# mainboard.net
KiCad netlist of a schematic drawn in EAGLE
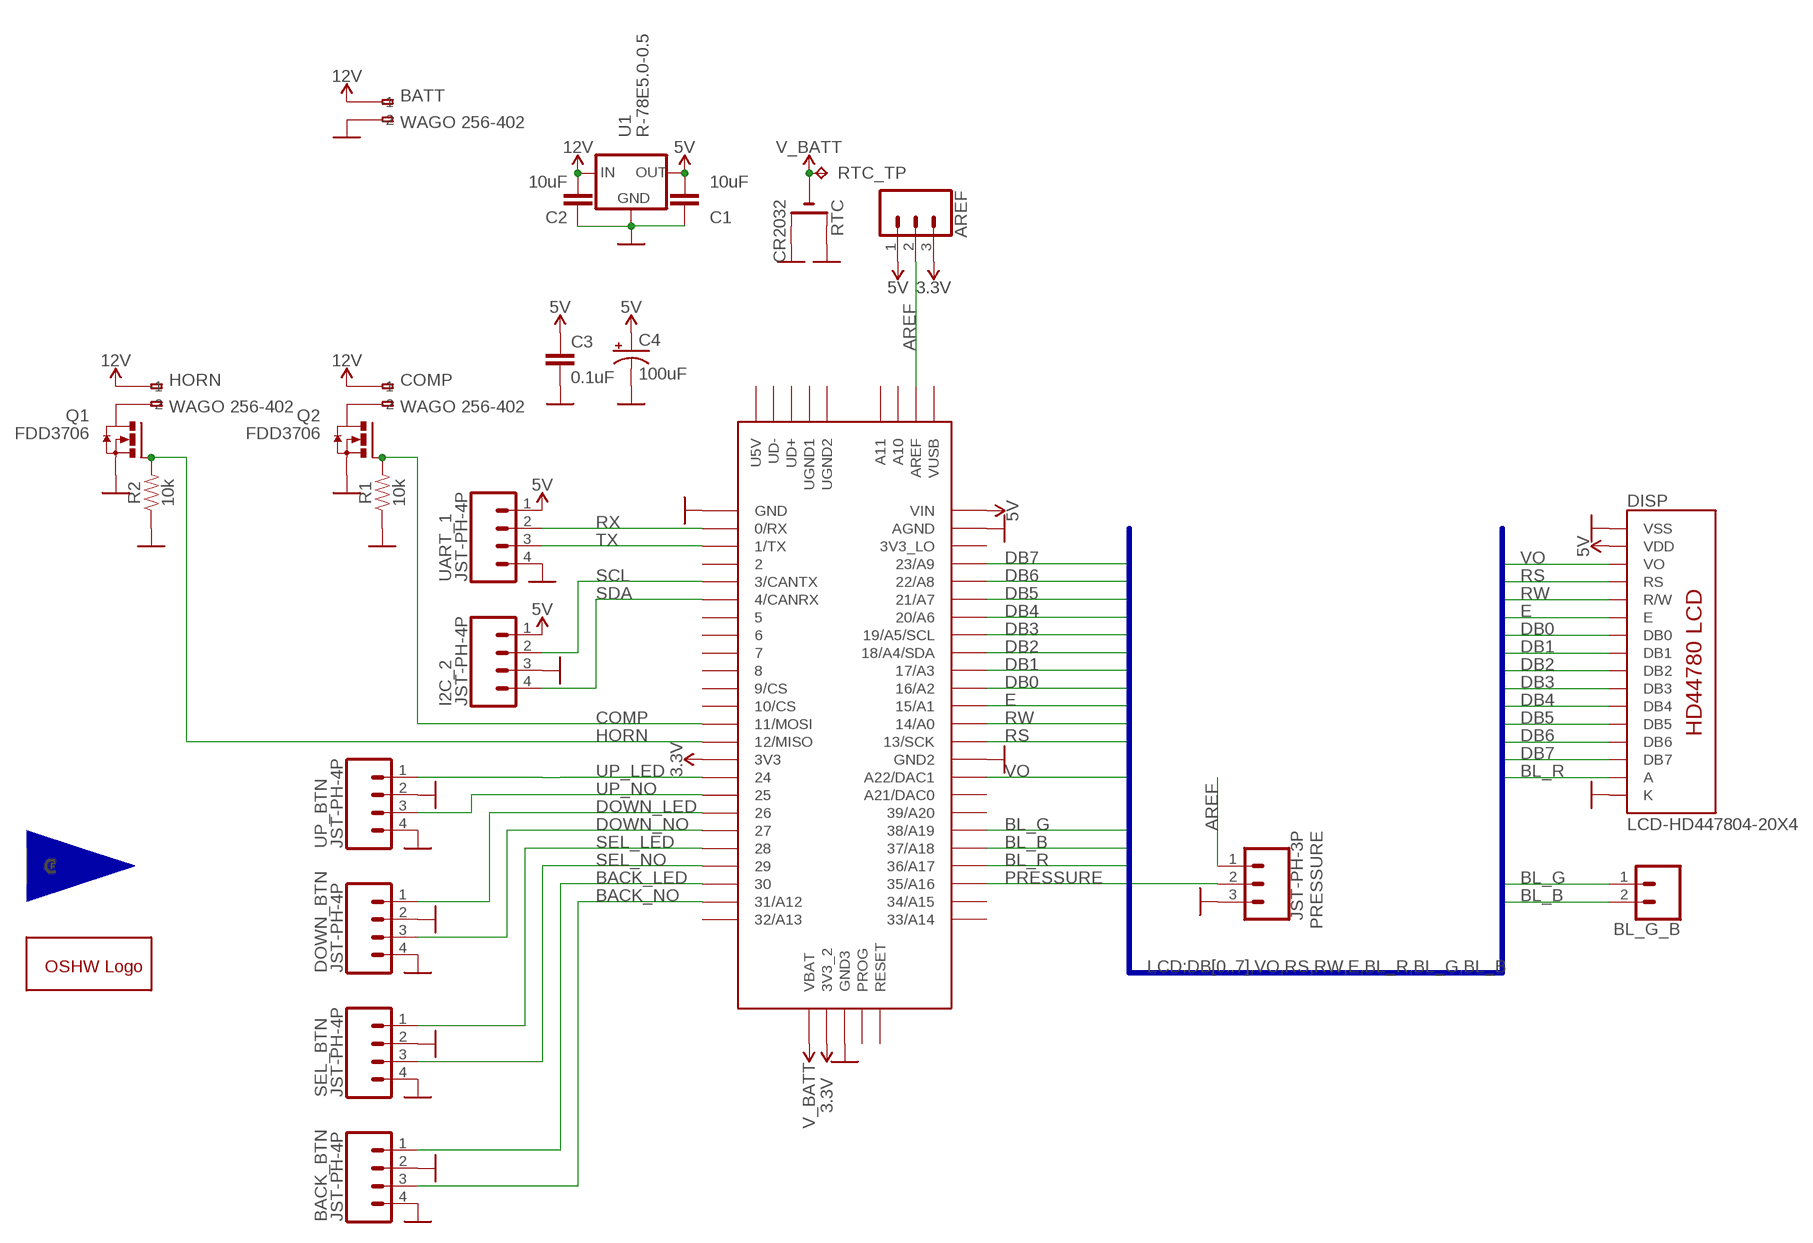
[diagram p0: schematic, sheet 1]

(export (version "E")
  (design (tool "Eeschema 10.0.6"))
  (components
    (comp (ref "AREF")
      (value "CONN_03LOCK")
      (footprint "eagle-import:1X03_LOCK")
      (libsource (lib "eagle-import") (part "CONN_03LOCK"))
    )
    (comp (ref "BACK_BTN")
      (value "JST-PH-4P")
      (footprint "eagle-import:JST-4-PTH-VERT")
      (libsource (lib "eagle-import") (part "CONN_04JST-PTH-VERT"))
    )
    (comp (ref "BATT")
      (value "WAGO 256-402")
      (footprint "eagle-import:255-402-5")
      (libsource (lib "eagle-import") (part "255-402-5"))
    )
    (comp (ref "BL_G_B")
      (value "CONN_02")
      (footprint "eagle-import:1X02")
      (libsource (lib "eagle-import") (part "CONN_02"))
    )
    (comp (ref "C1")
      (value "10uF")
      (footprint "eagle-import:0603")
      (libsource (lib "eagle-import") (part "10UF-0603-6.3V-20%"))
    )
    (comp (ref "C2")
      (value "10uF")
      (footprint "eagle-import:0603")
      (libsource (lib "eagle-import") (part "10UF-0603-6.3V-20%"))
    )
    (comp (ref "C3")
      (value "0.1uF")
      (footprint "eagle-import:0603")
      (libsource (lib "eagle-import") (part "0.1UF-0603-25V-(+80/-20%)"))
    )
    (comp (ref "C4")
      (value "100uF")
      (footprint "eagle-import:NIC_10X10.5_CAP")
      (libsource (lib "eagle-import") (part "100UF-POLAR-10X10.5-63V-20%"))
    )
    (comp (ref "COMP")
      (value "WAGO 256-402")
      (footprint "eagle-import:255-402-5")
      (libsource (lib "eagle-import") (part "255-402-5"))
    )
    (comp (ref "DISP")
      (value "LCD-HD447804-20X4")
      (footprint "eagle-import:LCD-20X4-4HOLES")
      (libsource (lib "eagle-import") (part "LCD-HD4478020X4-4HOLES4-HOLES"))
    )
    (comp (ref "DOWN_BTN")
      (value "JST-PH-4P")
      (footprint "eagle-import:JST-4-PTH-VERT")
      (libsource (lib "eagle-import") (part "CONN_04JST-PTH-VERT"))
    )
    (comp (ref "GOLD_ORB_SM1")
      (value "OSHWLOGOLOGO8MM")
      (footprint "eagle-import:OSHW_8MM")
      (libsource (lib "eagle-import") (part "OSHWLOGOLOGO8MM"))
    )
    (comp (ref "HORN")
      (value "WAGO 256-402")
      (footprint "eagle-import:255-402-5")
      (libsource (lib "eagle-import") (part "255-402-5"))
    )
    (comp (ref "I2C_2")
      (value "JST-PH-4P")
      (footprint "eagle-import:JST-4-PTH-VERT")
      (libsource (lib "eagle-import") (part "CONN_04JST-PTH-VERT"))
    )
    (comp (ref "PRESSURE")
      (value "JST-PH-3P")
      (footprint "eagle-import:JST-3-PTH-VERT")
      (libsource (lib "eagle-import") (part "CONN_03JST-PTH-VERT"))
    )
    (comp (ref "Q1")
      (value "FDD3706")
      (footprint "eagle-import:D2PACK")
      (libsource (lib "eagle-import") (part "IRF3704S"))
    )
    (comp (ref "Q2")
      (value "FDD3706")
      (footprint "eagle-import:D2PACK")
      (libsource (lib "eagle-import") (part "IRF3704S"))
    )
    (comp (ref "R1")
      (value "10k")
      (footprint "eagle-import:0603")
      (libsource (lib "eagle-import") (part "10KOHM-0603-1/10W-1%"))
    )
    (comp (ref "R2")
      (value "10k")
      (footprint "eagle-import:0603")
      (libsource (lib "eagle-import") (part "10KOHM-0603-1/10W-1%"))
    )
    (comp (ref "RTC")
      (value "CR2032")
      (footprint "eagle-import:CR2032-SMD")
      (libsource (lib "eagle-import") (part "CR2032SMT"))
    )
    (comp (ref "RTC_TP")
      (value "TPPAD1-17")
      (footprint "eagle-import:P1-17")
      (libsource (lib "eagle-import") (part "TPPAD1-17"))
    )
    (comp (ref "SEL_BTN")
      (value "JST-PH-4P")
      (footprint "eagle-import:JST-4-PTH-VERT")
      (libsource (lib "eagle-import") (part "CONN_04JST-PTH-VERT"))
    )
    (comp (ref "TEENSY")
      (value "TEENSY_3.5/3.6")
      (footprint "eagle-import:TEENSY_3.5_3.6")
      (libsource (lib "eagle-import") (part "TEENSY_3.5/3.6"))
    )
    (comp (ref "U$1")
      (value "CFLOGO")
      (footprint "eagle-import:CFLOGO")
      (libsource (lib "eagle-import") (part "CFLOGO"))
    )
    (comp (ref "U1")
      (value "R-78E5.0-0.5")
      (footprint "eagle-import:DC-DC_CONVERTER_78XX")
      (libsource (lib "eagle-import") (part "R-78E5.0-1.0"))
    )
    (comp (ref "UART_1")
      (value "JST-PH-4P")
      (footprint "eagle-import:JST-4-PTH-VERT")
      (libsource (lib "eagle-import") (part "CONN_04JST-PTH-VERT"))
    )
    (comp (ref "UP_BTN")
      (value "JST-PH-4P")
      (footprint "eagle-import:JST-4-PTH-VERT")
      (libsource (lib "eagle-import") (part "CONN_04JST-PTH-VERT"))
    )
  )
  (nets
    (net (code "1") (name "/AREF") (class "Default")
      (node (ref "AREF") (pin "2") (pinfunction "2_2") (pintype "passive"))
      (node (ref "PRESSURE") (pin "1") (pinfunction "1_1") (pintype "passive"))
      (node (ref "TEENSY") (pin "AREF") (pinfunction "AREF_AREF") (pintype "bidirectional"))
    )
    (net (code "2") (name "/BACK_LED") (class "Default")
      (node (ref "BACK_BTN") (pin "1") (pinfunction "1_1") (pintype "passive"))
      (node (ref "TEENSY") (pin "30") (pinfunction "30_30") (pintype "bidirectional"))
    )
    (net (code "3") (name "/BACK_NO") (class "Default")
      (node (ref "BACK_BTN") (pin "3") (pinfunction "3_3") (pintype "passive"))
      (node (ref "TEENSY") (pin "31/A12") (pinfunction "31/A12_31/A12") (pintype "bidirectional"))
    )
    (net (code "4") (name "/BL_B") (class "Default")
      (node (ref "BL_G_B") (pin "2") (pinfunction "2_2") (pintype "passive"))
      (node (ref "TEENSY") (pin "37/A18") (pinfunction "37/A18_37/A18") (pintype "bidirectional"))
    )
    (net (code "5") (name "/BL_G") (class "Default")
      (node (ref "BL_G_B") (pin "1") (pinfunction "1_1") (pintype "passive"))
      (node (ref "TEENSY") (pin "38/A19") (pinfunction "38/A19_38/A19") (pintype "bidirectional"))
    )
    (net (code "6") (name "/BL_R") (class "Default")
      (node (ref "DISP") (pin "P$15") (pinfunction "A_P$15") (pintype "power_in"))
      (node (ref "TEENSY") (pin "36/A17") (pinfunction "36/A17_36/A17") (pintype "bidirectional"))
    )
    (net (code "7") (name "/COMP") (class "Default")
      (node (ref "Q2") (pin "1") (pinfunction "G_1") (pintype "passive"))
      (node (ref "R1") (pin "2") (pinfunction "2_2") (pintype "passive"))
      (node (ref "TEENSY") (pin "11/MOSI") (pinfunction "11/MOSI_11/MOSI") (pintype "bidirectional"))
    )
    (net (code "8") (name "/DB0") (class "Default")
      (node (ref "DISP") (pin "P$7") (pinfunction "DB0_P$7") (pintype "bidirectional"))
      (node (ref "TEENSY") (pin "16/A2") (pinfunction "16/A2_16/A2") (pintype "bidirectional"))
    )
    (net (code "9") (name "/DB1") (class "Default")
      (node (ref "DISP") (pin "P$8") (pinfunction "DB1_P$8") (pintype "bidirectional"))
      (node (ref "TEENSY") (pin "17/A3") (pinfunction "17/A3_17/A3") (pintype "bidirectional"))
    )
    (net (code "10") (name "/DB2") (class "Default")
      (node (ref "DISP") (pin "P$9") (pinfunction "DB2_P$9") (pintype "bidirectional"))
      (node (ref "TEENSY") (pin "18/A4/SDA") (pinfunction "18/A4/SDA_18/A4/SDA") (pintype "bidirectional"))
    )
    (net (code "11") (name "/DB3") (class "Default")
      (node (ref "DISP") (pin "P$10") (pinfunction "DB3_P$10") (pintype "bidirectional"))
      (node (ref "TEENSY") (pin "19/A5/SCL") (pinfunction "19/A5/SCL_19/A5/SCL") (pintype "bidirectional"))
    )
    (net (code "12") (name "/DB4") (class "Default")
      (node (ref "DISP") (pin "P$11") (pinfunction "DB4_P$11") (pintype "bidirectional"))
      (node (ref "TEENSY") (pin "20/A6") (pinfunction "20/A6_20/A6") (pintype "bidirectional"))
    )
    (net (code "13") (name "/DB5") (class "Default")
      (node (ref "DISP") (pin "P$12") (pinfunction "DB5_P$12") (pintype "bidirectional"))
      (node (ref "TEENSY") (pin "21/A7") (pinfunction "21/A7_21/A7") (pintype "bidirectional"))
    )
    (net (code "14") (name "/DB6") (class "Default")
      (node (ref "DISP") (pin "P$13") (pinfunction "DB6_P$13") (pintype "bidirectional"))
      (node (ref "TEENSY") (pin "22/A8") (pinfunction "22/A8_22/A8") (pintype "bidirectional"))
    )
    (net (code "15") (name "/DB7") (class "Default")
      (node (ref "DISP") (pin "P$14") (pinfunction "DB7_P$14") (pintype "bidirectional"))
      (node (ref "TEENSY") (pin "23/A9") (pinfunction "23/A9_23/A9") (pintype "bidirectional"))
    )
    (net (code "16") (name "/DOWN_LED") (class "Default")
      (node (ref "DOWN_BTN") (pin "1") (pinfunction "1_1") (pintype "passive"))
      (node (ref "TEENSY") (pin "26") (pinfunction "26_26") (pintype "bidirectional"))
    )
    (net (code "17") (name "/DOWN_NO") (class "Default")
      (node (ref "DOWN_BTN") (pin "3") (pinfunction "3_3") (pintype "passive"))
      (node (ref "TEENSY") (pin "27") (pinfunction "27_27") (pintype "bidirectional"))
    )
    (net (code "18") (name "/E") (class "Default")
      (node (ref "DISP") (pin "P$6") (pinfunction "E_P$6") (pintype "input"))
      (node (ref "TEENSY") (pin "15/A1") (pinfunction "15/A1_15/A1") (pintype "bidirectional"))
    )
    (net (code "19") (name "/HORN") (class "Default")
      (node (ref "Q1") (pin "1") (pinfunction "G_1") (pintype "passive"))
      (node (ref "R2") (pin "2") (pinfunction "2_2") (pintype "passive"))
      (node (ref "TEENSY") (pin "12/MISO") (pinfunction "12/MISO_12/MISO") (pintype "bidirectional"))
    )
    (net (code "20") (name "/PRESSURE") (class "Default")
      (node (ref "PRESSURE") (pin "2") (pinfunction "2_2") (pintype "passive"))
      (node (ref "TEENSY") (pin "35/A16") (pinfunction "35/A16_35/A16") (pintype "bidirectional"))
    )
    (net (code "21") (name "/RS") (class "Default")
      (node (ref "DISP") (pin "P$4") (pinfunction "RS_P$4") (pintype "input"))
      (node (ref "TEENSY") (pin "13/SCK") (pinfunction "13/SCK_13/SCK") (pintype "bidirectional"))
    )
    (net (code "22") (name "/RW") (class "Default")
      (node (ref "DISP") (pin "P$5") (pinfunction "R/W_P$5") (pintype "input"))
      (node (ref "TEENSY") (pin "14/A0") (pinfunction "14/A0_14/A0") (pintype "bidirectional"))
    )
    (net (code "23") (name "/RX") (class "Default")
      (node (ref "TEENSY") (pin "0/RX") (pinfunction "0/RX_0/RX") (pintype "bidirectional"))
      (node (ref "UART_1") (pin "2") (pinfunction "2_2") (pintype "passive"))
    )
    (net (code "24") (name "/SCL") (class "Default")
      (node (ref "I2C_2") (pin "2") (pinfunction "2_2") (pintype "passive"))
      (node (ref "TEENSY") (pin "3/CANTX") (pinfunction "3/CANTX_3/CANTX") (pintype "bidirectional"))
    )
    (net (code "25") (name "/SDA") (class "Default")
      (node (ref "I2C_2") (pin "4") (pinfunction "4_4") (pintype "passive"))
      (node (ref "TEENSY") (pin "4/CANRX") (pinfunction "4/CANRX_4/CANRX") (pintype "bidirectional"))
    )
    (net (code "26") (name "/SEL_LED") (class "Default")
      (node (ref "SEL_BTN") (pin "1") (pinfunction "1_1") (pintype "passive"))
      (node (ref "TEENSY") (pin "28") (pinfunction "28_28") (pintype "bidirectional"))
    )
    (net (code "27") (name "/SEL_NO") (class "Default")
      (node (ref "SEL_BTN") (pin "3") (pinfunction "3_3") (pintype "passive"))
      (node (ref "TEENSY") (pin "29") (pinfunction "29_29") (pintype "bidirectional"))
    )
    (net (code "28") (name "/TX") (class "Default")
      (node (ref "TEENSY") (pin "1/TX") (pinfunction "1/TX_1/TX") (pintype "bidirectional"))
      (node (ref "UART_1") (pin "3") (pinfunction "3_3") (pintype "passive"))
    )
    (net (code "29") (name "/UP_LED") (class "Default")
      (node (ref "TEENSY") (pin "24") (pinfunction "24_24") (pintype "bidirectional"))
      (node (ref "UP_BTN") (pin "1") (pinfunction "1_1") (pintype "passive"))
    )
    (net (code "30") (name "/UP_NO") (class "Default")
      (node (ref "TEENSY") (pin "25") (pinfunction "25_25") (pintype "bidirectional"))
      (node (ref "UP_BTN") (pin "3") (pinfunction "3_3") (pintype "passive"))
    )
    (net (code "31") (name "/VO") (class "Default")
      (node (ref "DISP") (pin "P$3") (pinfunction "VO_P$3") (pintype "bidirectional"))
      (node (ref "TEENSY") (pin "A22/DAC1") (pinfunction "A22/DAC1_A22/DAC1") (pintype "bidirectional"))
    )
    (net (code "33") (name "3.3V") (class "Default")
      (node (ref "AREF") (pin "3") (pinfunction "3_3") (pintype "passive"))
      (node (ref "TEENSY") (pin "3V3") (pinfunction "3V3_3V3") (pintype "bidirectional"))
      (node (ref "TEENSY") (pin "3V3_2") (pinfunction "3V3_2_3V3_2") (pintype "bidirectional"))
    )
    (net (code "34") (name "5V") (class "Default")
      (node (ref "AREF") (pin "1") (pinfunction "1_1") (pintype "passive"))
      (node (ref "C1") (pin "2") (pinfunction "2_2") (pintype "passive"))
      (node (ref "C3") (pin "1") (pinfunction "1_1") (pintype "passive"))
      (node (ref "C4") (pin "+") (pinfunction "+_+") (pintype "passive"))
      (node (ref "DISP") (pin "P$2") (pinfunction "VDD_P$2") (pintype "power_in"))
      (node (ref "I2C_2") (pin "1") (pinfunction "1_1") (pintype "passive"))
      (node (ref "TEENSY") (pin "VIN") (pinfunction "VIN_VIN") (pintype "bidirectional"))
      (node (ref "U1") (pin "VOUT") (pinfunction "OUT_VOUT") (pintype "passive"))
      (node (ref "UART_1") (pin "1") (pinfunction "1_1") (pintype "passive"))
    )
    (net (code "35") (name "12V") (class "Default")
      (node (ref "BATT") (pin "A1") (pinfunction "-1_A1") (pintype "passive"))
      (node (ref "C2") (pin "2") (pinfunction "2_2") (pintype "passive"))
      (node (ref "COMP") (pin "A1") (pinfunction "-1_A1") (pintype "passive"))
      (node (ref "HORN") (pin "A1") (pinfunction "-1_A1") (pintype "passive"))
      (node (ref "U1") (pin "VIN") (pinfunction "IN_VIN") (pintype "input"))
    )
    (net (code "36") (name "GND") (class "Default")
      (node (ref "BACK_BTN") (pin "2") (pinfunction "2_2") (pintype "passive"))
      (node (ref "BACK_BTN") (pin "4") (pinfunction "4_4") (pintype "passive"))
      (node (ref "BATT") (pin "A2") (pinfunction "-2_A2") (pintype "passive"))
      (node (ref "C1") (pin "1") (pinfunction "1_1") (pintype "passive"))
      (node (ref "C2") (pin "1") (pinfunction "1_1") (pintype "passive"))
      (node (ref "C3") (pin "2") (pinfunction "2_2") (pintype "passive"))
      (node (ref "C4") (pin "-") (pinfunction "-_-") (pintype "passive"))
      (node (ref "DISP") (pin "P$1") (pinfunction "VSS_P$1") (pintype "power_in"))
      (node (ref "DISP") (pin "P$16") (pinfunction "K_P$16") (pintype "power_in"))
      (node (ref "DOWN_BTN") (pin "2") (pinfunction "2_2") (pintype "passive"))
      (node (ref "DOWN_BTN") (pin "4") (pinfunction "4_4") (pintype "passive"))
      (node (ref "I2C_2") (pin "3") (pinfunction "3_3") (pintype "passive"))
      (node (ref "PRESSURE") (pin "3") (pinfunction "3_3") (pintype "passive"))
      (node (ref "Q1") (pin "3") (pinfunction "S_3") (pintype "passive"))
      (node (ref "Q2") (pin "3") (pinfunction "S_3") (pintype "passive"))
      (node (ref "R1") (pin "1") (pinfunction "1_1") (pintype "passive"))
      (node (ref "R2") (pin "1") (pinfunction "1_1") (pintype "passive"))
      (node (ref "RTC") (pin "+$1") (pinfunction "+_+$1") (pintype "passive"))
      (node (ref "RTC") (pin "+$2") (pinfunction "+1_+$2") (pintype "passive"))
      (node (ref "SEL_BTN") (pin "2") (pinfunction "2_2") (pintype "passive"))
      (node (ref "SEL_BTN") (pin "4") (pinfunction "4_4") (pintype "passive"))
      (node (ref "TEENSY") (pin "AGND") (pinfunction "AGND_AGND") (pintype "bidirectional"))
      (node (ref "TEENSY") (pin "GND") (pinfunction "GND_GND") (pintype "bidirectional"))
      (node (ref "TEENSY") (pin "GND2") (pinfunction "GND2_GND2") (pintype "bidirectional"))
      (node (ref "TEENSY") (pin "GND3") (pinfunction "GND3_GND3") (pintype "bidirectional"))
      (node (ref "U1") (pin "GND") (pinfunction "GND_GND") (pintype "input"))
      (node (ref "UART_1") (pin "4") (pinfunction "4_4") (pintype "passive"))
      (node (ref "UP_BTN") (pin "2") (pinfunction "2_2") (pintype "passive"))
      (node (ref "UP_BTN") (pin "4") (pinfunction "4_4") (pintype "passive"))
    )
    (net (code "37") (name "Net-(COMP--2)") (class "Default")
      (node (ref "COMP") (pin "A2") (pinfunction "-2_A2") (pintype "passive"))
      (node (ref "Q2") (pin "2") (pinfunction "D_2") (pintype "passive"))
    )
    (net (code "38") (name "Net-(HORN--2)") (class "Default")
      (node (ref "HORN") (pin "A2") (pinfunction "-2_A2") (pintype "passive"))
      (node (ref "Q1") (pin "2") (pinfunction "D_2") (pintype "passive"))
    )
    (net (code "39") (name "V_BATT") (class "Default")
      (node (ref "RTC") (pin "-") (pinfunction "-_-") (pintype "passive"))
      (node (ref "RTC_TP") (pin "TP") (pinfunction "TP_TP") (pintype "input"))
      (node (ref "TEENSY") (pin "VBAT") (pinfunction "VBAT_VBAT") (pintype "bidirectional"))
    )
    (net (code "40") (name "unconnected-(BATT-B-1-PadB1)") (class "Default")
      (node (ref "BATT") (pin "B1") (pinfunction "B-1_B1") (pintype "passive"))
    )
    (net (code "41") (name "unconnected-(BATT-B-2-PadB2)") (class "Default")
      (node (ref "BATT") (pin "B2") (pinfunction "B-2_B2") (pintype "passive"))
    )
    (net (code "42") (name "unconnected-(COMP-B-1-PadB1)") (class "Default")
      (node (ref "COMP") (pin "B1") (pinfunction "B-1_B1") (pintype "passive"))
    )
    (net (code "43") (name "unconnected-(COMP-B-2-PadB2)") (class "Default")
      (node (ref "COMP") (pin "B2") (pinfunction "B-2_B2") (pintype "passive"))
    )
    (net (code "44") (name "unconnected-(HORN-B-1-PadB1)") (class "Default")
      (node (ref "HORN") (pin "B1") (pinfunction "B-1_B1") (pintype "passive"))
    )
    (net (code "45") (name "unconnected-(HORN-B-2-PadB2)") (class "Default")
      (node (ref "HORN") (pin "B2") (pinfunction "B-2_B2") (pintype "passive"))
    )
    (net (code "46") (name "unconnected-(TEENSY-A21{slash}DAC0-Pad21{slash}DAC0)") (class "Default")
      (node (ref "TEENSY") (pin "21/DAC0") (pinfunction "A21/DAC0_21/DAC0") (pintype "bidirectional"))
    )
    (net (code "47") (name "unconnected-(TEENSY-Pad2)") (class "Default")
      (node (ref "TEENSY") (pin "2") (pinfunction "2_2") (pintype "bidirectional"))
    )
    (net (code "48") (name "unconnected-(TEENSY-Pad3V3_LO)") (class "Default")
      (node (ref "TEENSY") (pin "3V3_LO") (pinfunction "3V3_LO_3V3_LO") (pintype "bidirectional"))
    )
    (net (code "49") (name "unconnected-(TEENSY-Pad5)") (class "Default")
      (node (ref "TEENSY") (pin "5") (pinfunction "5_5") (pintype "bidirectional"))
    )
    (net (code "50") (name "unconnected-(TEENSY-Pad6)") (class "Default")
      (node (ref "TEENSY") (pin "6") (pinfunction "6_6") (pintype "bidirectional"))
    )
    (net (code "51") (name "unconnected-(TEENSY-Pad7)") (class "Default")
      (node (ref "TEENSY") (pin "7") (pinfunction "7_7") (pintype "bidirectional"))
    )
    (net (code "52") (name "unconnected-(TEENSY-Pad8)") (class "Default")
      (node (ref "TEENSY") (pin "8") (pinfunction "8_8") (pintype "bidirectional"))
    )
    (net (code "53") (name "unconnected-(TEENSY-Pad9{slash}CS)") (class "Default")
      (node (ref "TEENSY") (pin "9/CS") (pinfunction "9/CS_9/CS") (pintype "bidirectional"))
    )
    (net (code "54") (name "unconnected-(TEENSY-Pad10{slash}CS)") (class "Default")
      (node (ref "TEENSY") (pin "10/CS") (pinfunction "10/CS_10/CS") (pintype "bidirectional"))
    )
    (net (code "55") (name "unconnected-(TEENSY-Pad32{slash}A13)") (class "Default")
      (node (ref "TEENSY") (pin "32/A13") (pinfunction "32/A13_32/A13") (pintype "bidirectional"))
    )
    (net (code "56") (name "unconnected-(TEENSY-Pad33{slash}A14)") (class "Default")
      (node (ref "TEENSY") (pin "33/A14") (pinfunction "33/A14_33/A14") (pintype "bidirectional"))
    )
    (net (code "57") (name "unconnected-(TEENSY-Pad34{slash}A15)") (class "Default")
      (node (ref "TEENSY") (pin "34/A15") (pinfunction "34/A15_34/A15") (pintype "bidirectional"))
    )
    (net (code "58") (name "unconnected-(TEENSY-Pad39{slash}A20)") (class "Default")
      (node (ref "TEENSY") (pin "39/A20") (pinfunction "39/A20_39/A20") (pintype "bidirectional"))
    )
    (net (code "59") (name "unconnected-(TEENSY-PadA10)") (class "Default")
      (node (ref "TEENSY") (pin "A10") (pinfunction "A10_A10") (pintype "bidirectional"))
    )
    (net (code "60") (name "unconnected-(TEENSY-PadA11)") (class "Default")
      (node (ref "TEENSY") (pin "A11") (pinfunction "A11_A11") (pintype "bidirectional"))
    )
    (net (code "61") (name "unconnected-(TEENSY-PadPROG)") (class "Default")
      (node (ref "TEENSY") (pin "PROG") (pinfunction "PROG_PROG") (pintype "bidirectional"))
    )
    (net (code "62") (name "unconnected-(TEENSY-PadRESET)") (class "Default")
      (node (ref "TEENSY") (pin "RESET") (pinfunction "RESET_RESET") (pintype "bidirectional"))
    )
    (net (code "63") (name "unconnected-(TEENSY-PadU5V)") (class "Default")
      (node (ref "TEENSY") (pin "U5V") (pinfunction "U5V_U5V") (pintype "bidirectional"))
    )
    (net (code "64") (name "unconnected-(TEENSY-PadUD+)") (class "Default")
      (node (ref "TEENSY") (pin "UD+") (pinfunction "UD+_UD+") (pintype "bidirectional"))
    )
    (net (code "65") (name "unconnected-(TEENSY-PadUD-)") (class "Default")
      (node (ref "TEENSY") (pin "UD-") (pinfunction "UD-_UD-") (pintype "bidirectional"))
    )
    (net (code "66") (name "unconnected-(TEENSY-PadUGND1)") (class "Default")
      (node (ref "TEENSY") (pin "UGND1") (pinfunction "UGND1_UGND1") (pintype "bidirectional"))
    )
    (net (code "67") (name "unconnected-(TEENSY-PadUGND2)") (class "Default")
      (node (ref "TEENSY") (pin "UGND2") (pinfunction "UGND2_UGND2") (pintype "bidirectional"))
    )
    (net (code "68") (name "unconnected-(TEENSY-PadVUSB)") (class "Default")
      (node (ref "TEENSY") (pin "VUSB") (pinfunction "VUSB_VUSB") (pintype "bidirectional"))
    )
  )
)
